# dc26_maneki-neko_badge_page01_2018060723.net
KiCad netlist of a schematic drawn in EAGLE
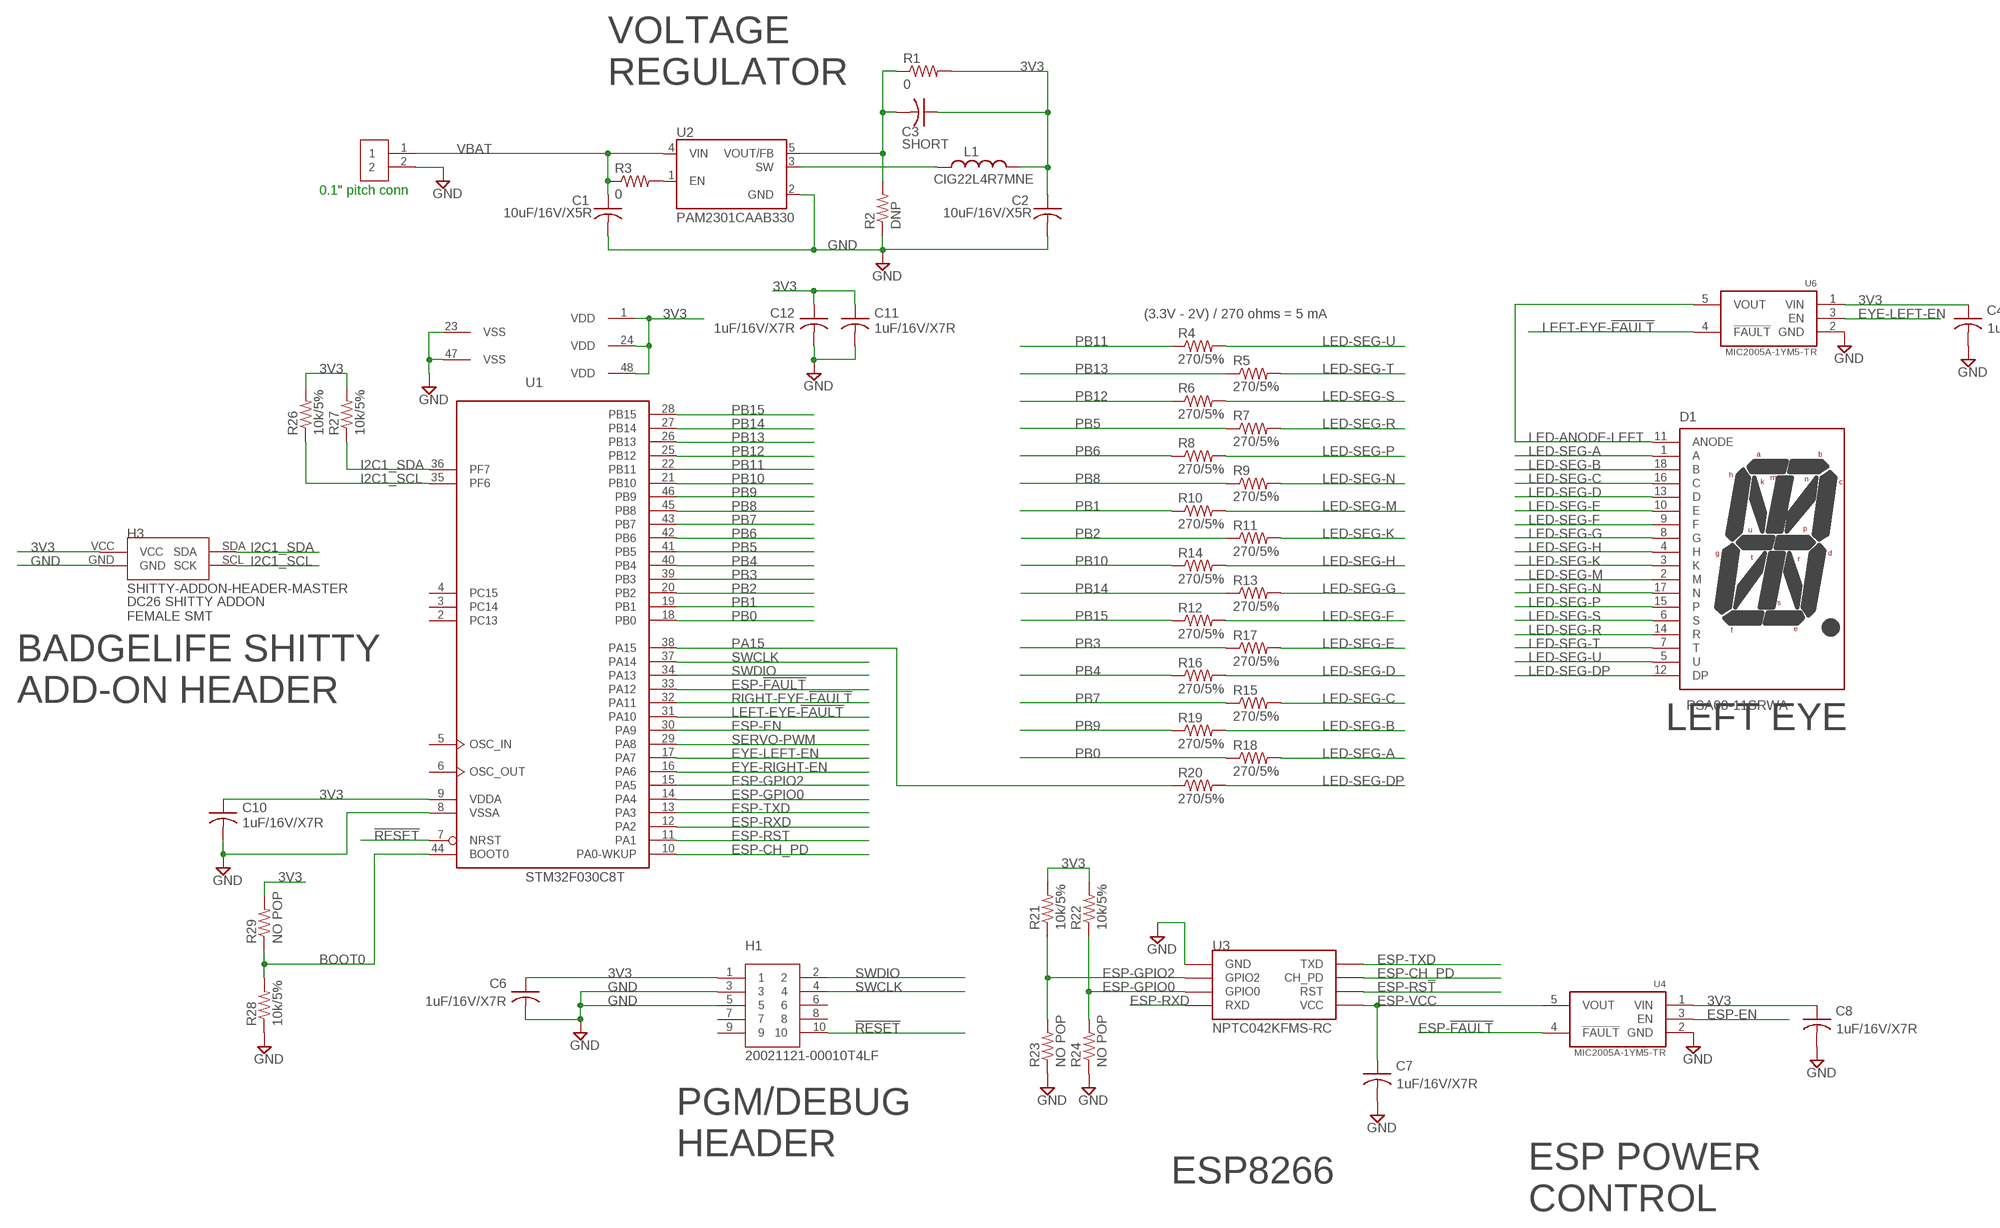
[diagram p0: schematic, sheet 1, part 1 of 2]
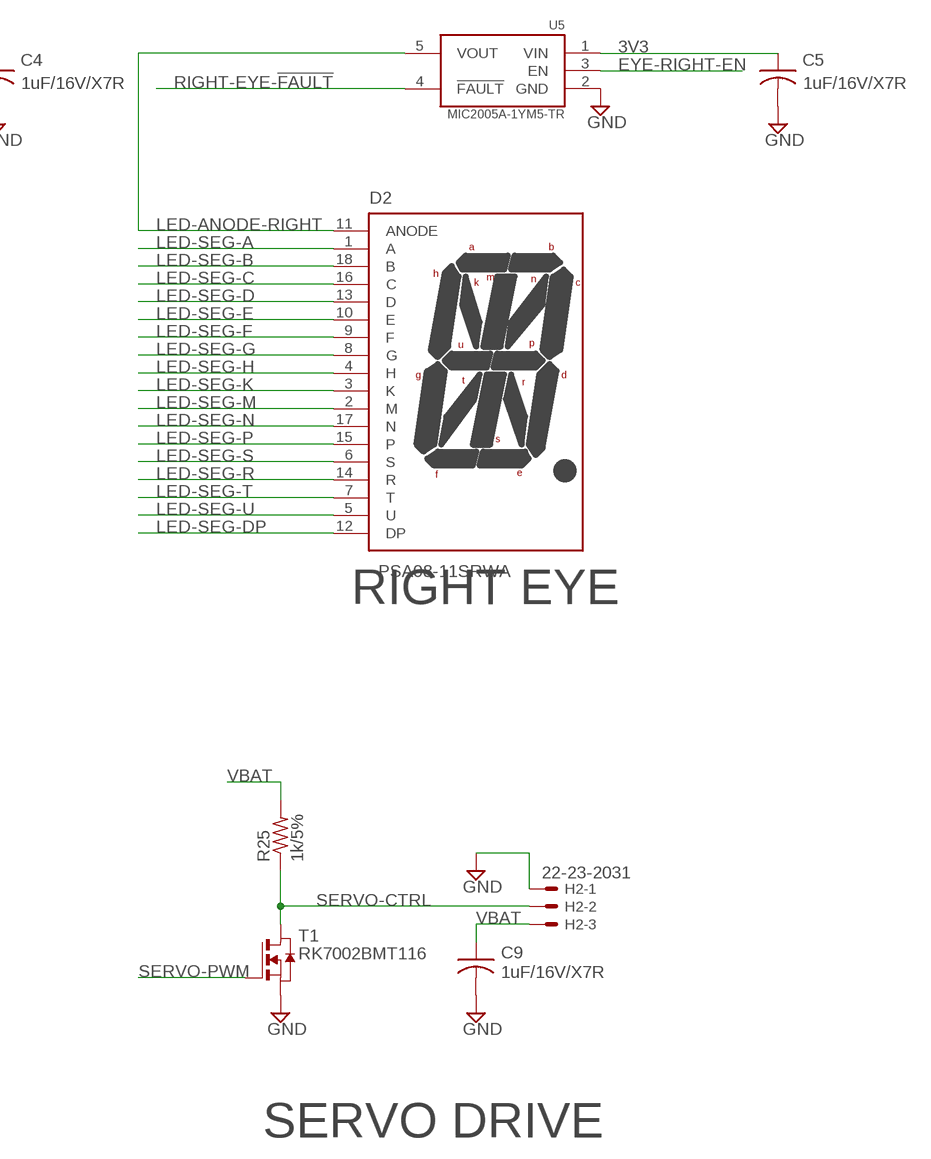
[diagram p1: schematic, sheet 1, part 2 of 2]

(export (version "E")
  (design (tool "Eeschema 10.0.6"))
  (components
    (comp (ref "C1")
      (value "10uF/16V/X5R")
      (footprint "eagle-import:C0805")
      (libsource (lib "eagle-import") (part "C-USC0805"))
    )
    (comp (ref "C2")
      (value "10uF/16V/X5R")
      (footprint "eagle-import:C0805")
      (libsource (lib "eagle-import") (part "C-USC0805"))
    )
    (comp (ref "C3")
      (value "SHORT")
      (footprint "eagle-import:C0805")
      (libsource (lib "eagle-import") (part "C-USC0805"))
    )
    (comp (ref "C4")
      (value "1uF/16V/X7R")
      (footprint "eagle-import:C0805")
      (libsource (lib "eagle-import") (part "C-USC0805"))
    )
    (comp (ref "C5")
      (value "1uF/16V/X7R")
      (footprint "eagle-import:C0805")
      (libsource (lib "eagle-import") (part "C-USC0805"))
    )
    (comp (ref "C6")
      (value "1uF/16V/X7R")
      (footprint "eagle-import:C0805")
      (libsource (lib "eagle-import") (part "C-USC0805"))
    )
    (comp (ref "C7")
      (value "1uF/16V/X7R")
      (footprint "eagle-import:C0805")
      (libsource (lib "eagle-import") (part "C-USC0805"))
    )
    (comp (ref "C8")
      (value "1uF/16V/X7R")
      (footprint "eagle-import:C0805")
      (libsource (lib "eagle-import") (part "C-USC0805"))
    )
    (comp (ref "C9")
      (value "1uF/16V/X7R")
      (footprint "eagle-import:C0805")
      (libsource (lib "eagle-import") (part "C-USC0805"))
    )
    (comp (ref "C10")
      (value "1uF/16V/X7R")
      (footprint "eagle-import:C0805")
      (libsource (lib "eagle-import") (part "C-USC0805"))
    )
    (comp (ref "C11")
      (value "1uF/16V/X7R")
      (footprint "eagle-import:C0805")
      (libsource (lib "eagle-import") (part "C-USC0805"))
    )
    (comp (ref "C12")
      (value "1uF/16V/X7R")
      (footprint "eagle-import:C0805")
      (libsource (lib "eagle-import") (part "C-USC0805"))
    )
    (comp (ref "D1")
      (value "PSA08-11SRWA")
      (footprint "eagle-import:PSA08-11SRWA")
      (libsource (lib "eagle-import") (part "PSA08-11SRWA"))
    )
    (comp (ref "D2")
      (value "PSA08-11SRWA")
      (footprint "eagle-import:PSA08-11SRWA")
      (libsource (lib "eagle-import") (part "PSA08-11SRWA"))
    )
    (comp (ref "H1")
      (value "20021121-00010T4LF")
      (footprint "eagle-import:20021121-00010T4LF")
      (libsource (lib "eagle-import") (part "20021121-00010T4LF"))
    )
    (comp (ref "H2")
      (value "22-23-2031")
      (footprint "eagle-import:22-23-2031")
      (fields (field (name "MF") "MOLEX"))
      (libsource (lib "eagle-import") (part "22-23-2031"))
    )
    (comp (ref "H3")
      (value "SHITTY-ADDON-HEADER-MASTER")
      (footprint "eagle-import:2X2-0.1INCH-FEMALE-SMT")
      (libsource (lib "eagle-import") (part "SHITTY-ADDON-HEADER-MASTER"))
    )
    (comp (ref "L1")
      (value "CIG22L4R7MNE")
      (footprint "eagle-import:L-1008-US")
      (libsource (lib "eagle-import") (part "CIG22L4R7MNE"))
    )
    (comp (ref "R1")
      (value "0")
      (footprint "eagle-import:R0805")
      (libsource (lib "eagle-import") (part "R-US_R0805"))
    )
    (comp (ref "R2")
      (value "DNP")
      (footprint "eagle-import:R0805")
      (libsource (lib "eagle-import") (part "R-US_R0805"))
    )
    (comp (ref "R3")
      (value "0")
      (footprint "eagle-import:R0805")
      (libsource (lib "eagle-import") (part "R-US_R0805"))
    )
    (comp (ref "R4")
      (value "270/5%")
      (footprint "eagle-import:R0805")
      (libsource (lib "eagle-import") (part "R-US_R0805"))
    )
    (comp (ref "R5")
      (value "270/5%")
      (footprint "eagle-import:R0805")
      (libsource (lib "eagle-import") (part "R-US_R0805"))
    )
    (comp (ref "R6")
      (value "270/5%")
      (footprint "eagle-import:R0805")
      (libsource (lib "eagle-import") (part "R-US_R0805"))
    )
    (comp (ref "R7")
      (value "270/5%")
      (footprint "eagle-import:R0805")
      (libsource (lib "eagle-import") (part "R-US_R0805"))
    )
    (comp (ref "R8")
      (value "270/5%")
      (footprint "eagle-import:R0805")
      (libsource (lib "eagle-import") (part "R-US_R0805"))
    )
    (comp (ref "R9")
      (value "270/5%")
      (footprint "eagle-import:R0805")
      (libsource (lib "eagle-import") (part "R-US_R0805"))
    )
    (comp (ref "R10")
      (value "270/5%")
      (footprint "eagle-import:R0805")
      (libsource (lib "eagle-import") (part "R-US_R0805"))
    )
    (comp (ref "R11")
      (value "270/5%")
      (footprint "eagle-import:R0805")
      (libsource (lib "eagle-import") (part "R-US_R0805"))
    )
    (comp (ref "R12")
      (value "270/5%")
      (footprint "eagle-import:R0805")
      (libsource (lib "eagle-import") (part "R-US_R0805"))
    )
    (comp (ref "R13")
      (value "270/5%")
      (footprint "eagle-import:R0805")
      (libsource (lib "eagle-import") (part "R-US_R0805"))
    )
    (comp (ref "R14")
      (value "270/5%")
      (footprint "eagle-import:R0805")
      (libsource (lib "eagle-import") (part "R-US_R0805"))
    )
    (comp (ref "R15")
      (value "270/5%")
      (footprint "eagle-import:R0805")
      (libsource (lib "eagle-import") (part "R-US_R0805"))
    )
    (comp (ref "R16")
      (value "270/5%")
      (footprint "eagle-import:R0805")
      (libsource (lib "eagle-import") (part "R-US_R0805"))
    )
    (comp (ref "R17")
      (value "270/5%")
      (footprint "eagle-import:R0805")
      (libsource (lib "eagle-import") (part "R-US_R0805"))
    )
    (comp (ref "R18")
      (value "270/5%")
      (footprint "eagle-import:R0805")
      (libsource (lib "eagle-import") (part "R-US_R0805"))
    )
    (comp (ref "R19")
      (value "270/5%")
      (footprint "eagle-import:R0805")
      (libsource (lib "eagle-import") (part "R-US_R0805"))
    )
    (comp (ref "R20")
      (value "270/5%")
      (footprint "eagle-import:R0805")
      (libsource (lib "eagle-import") (part "R-US_R0805"))
    )
    (comp (ref "R21")
      (value "10k/5%")
      (footprint "eagle-import:R0805")
      (libsource (lib "eagle-import") (part "R-US_R0805"))
    )
    (comp (ref "R22")
      (value "10k/5%")
      (footprint "eagle-import:R0805")
      (libsource (lib "eagle-import") (part "R-US_R0805"))
    )
    (comp (ref "R23")
      (value "NO POP")
      (footprint "eagle-import:R0805")
      (libsource (lib "eagle-import") (part "R-US_R0805"))
    )
    (comp (ref "R24")
      (value "NO POP")
      (footprint "eagle-import:R0805")
      (libsource (lib "eagle-import") (part "R-US_R0805"))
    )
    (comp (ref "R25")
      (value "1k/5%")
      (footprint "eagle-import:R0805")
      (libsource (lib "eagle-import") (part "R-US_R0805"))
    )
    (comp (ref "R26")
      (value "10k/5%")
      (footprint "eagle-import:R0805")
      (libsource (lib "eagle-import") (part "R-US_R0805"))
    )
    (comp (ref "R27")
      (value "10k/5%")
      (footprint "eagle-import:R0805")
      (libsource (lib "eagle-import") (part "R-US_R0805"))
    )
    (comp (ref "R28")
      (value "10k/5%")
      (footprint "eagle-import:R0805")
      (libsource (lib "eagle-import") (part "R-US_R0805"))
    )
    (comp (ref "R29")
      (value "NO POP")
      (footprint "eagle-import:R0805")
      (libsource (lib "eagle-import") (part "R-US_R0805"))
    )
    (comp (ref "T1")
      (value "RK7002BMT116")
      (footprint "eagle-import:SOT-23")
      (libsource (lib "eagle-import") (part "NMOSSOT23"))
    )
    (comp (ref "U$1")
      (value "BATTPADS-SMT")
      (footprint "eagle-import:BATTPADS-SMT")
      (libsource (lib "eagle-import") (part "BATTPADS-SMT"))
    )
    (comp (ref "U1")
      (value "STM32F030C8T")
      (footprint "eagle-import:LQFP48")
      (libsource (lib "eagle-import") (part "STM32F030CT8"))
    )
    (comp (ref "U2")
      (value "PAM2301CAAB330")
      (footprint "eagle-import:SOT95P280X100-5N")
      (libsource (lib "eagle-import") (part "PAM2301CAAB330"))
    )
    (comp (ref "U3")
      (value "NPTC042KFMS-RC")
      (footprint "eagle-import:NPTC042KFMS-RC")
      (libsource (lib "eagle-import") (part "NPTC042KFMS-RC"))
    )
    (comp (ref "U4")
      (value "MIC2005A-1YM5-TR")
      (footprint "eagle-import:SOT95P270X145-5N")
      (libsource (lib "eagle-import") (part "MIC2005A-1YM5-TR"))
    )
    (comp (ref "U5")
      (value "MIC2005A-1YM5-TR")
      (footprint "eagle-import:SOT95P270X145-5N")
      (libsource (lib "eagle-import") (part "MIC2005A-1YM5-TR"))
    )
    (comp (ref "U6")
      (value "MIC2005A-1YM5-TR")
      (footprint "eagle-import:SOT95P270X145-5N")
      (libsource (lib "eagle-import") (part "MIC2005A-1YM5-TR"))
    )
  )
  (nets
    (net (code "1") (name "/3V3") (class "Default")
      (node (ref "C10") (pin "1") (pinfunction "1_1") (pintype "passive"))
      (node (ref "C11") (pin "1") (pinfunction "1_1") (pintype "passive"))
      (node (ref "C12") (pin "1") (pinfunction "1_1") (pintype "passive"))
      (node (ref "C2") (pin "1") (pinfunction "1_1") (pintype "passive"))
      (node (ref "C3") (pin "1") (pinfunction "1_1") (pintype "passive"))
      (node (ref "C4") (pin "1") (pinfunction "1_1") (pintype "passive"))
      (node (ref "C5") (pin "1") (pinfunction "1_1") (pintype "passive"))
      (node (ref "C6") (pin "1") (pinfunction "1_1") (pintype "passive"))
      (node (ref "C8") (pin "1") (pinfunction "1_1") (pintype "passive"))
      (node (ref "H1") (pin "1") (pinfunction "1_1") (pintype "bidirectional"))
      (node (ref "H3") (pin "VCC") (pinfunction "VCC_VCC") (pintype "bidirectional"))
      (node (ref "L1") (pin "P$2") (pinfunction "2_P$2") (pintype "passive"))
      (node (ref "R1") (pin "2") (pinfunction "2_2") (pintype "passive"))
      (node (ref "R21") (pin "2") (pinfunction "2_2") (pintype "passive"))
      (node (ref "R22") (pin "2") (pinfunction "2_2") (pintype "passive"))
      (node (ref "R26") (pin "2") (pinfunction "2_2") (pintype "passive"))
      (node (ref "R27") (pin "2") (pinfunction "2_2") (pintype "passive"))
      (node (ref "R29") (pin "2") (pinfunction "2_2") (pintype "passive"))
      (node (ref "U1") (pin "1") (pinfunction "VDD_1") (pintype "power_in"))
      (node (ref "U1") (pin "24") (pinfunction "VDD_24") (pintype "power_in"))
      (node (ref "U1") (pin "48") (pinfunction "VDD_48") (pintype "power_in"))
      (node (ref "U1") (pin "9") (pinfunction "VDDA_9") (pintype "power_in"))
      (node (ref "U4") (pin "1") (pinfunction "VIN_1") (pintype "bidirectional"))
      (node (ref "U5") (pin "1") (pinfunction "VIN_1") (pintype "bidirectional"))
      (node (ref "U6") (pin "1") (pinfunction "VIN_1") (pintype "bidirectional"))
    )
    (net (code "2") (name "/BOOT0") (class "Default")
      (node (ref "R28") (pin "2") (pinfunction "2_2") (pintype "passive"))
      (node (ref "R29") (pin "1") (pinfunction "1_1") (pintype "passive"))
      (node (ref "U1") (pin "44") (pinfunction "BOOT0_44") (pintype "input"))
    )
    (net (code "3") (name "/ESP-CH_PD") (class "Default")
      (node (ref "U1") (pin "10") (pinfunction "PA0-WKUP_10") (pintype "bidirectional"))
      (node (ref "U3") (pin "3") (pinfunction "CH_PD_3") (pintype "bidirectional"))
    )
    (net (code "4") (name "/ESP-EN") (class "Default")
      (node (ref "U1") (pin "30") (pinfunction "PA9_30") (pintype "bidirectional"))
      (node (ref "U4") (pin "3") (pinfunction "EN_3") (pintype "bidirectional"))
    )
    (net (code "5") (name "/ESP-GPIO0") (class "Default")
      (node (ref "R22") (pin "1") (pinfunction "1_1") (pintype "passive"))
      (node (ref "R24") (pin "2") (pinfunction "2_2") (pintype "passive"))
      (node (ref "U1") (pin "14") (pinfunction "PA4_14") (pintype "bidirectional"))
      (node (ref "U3") (pin "6") (pinfunction "GPIO0_6") (pintype "bidirectional"))
    )
    (net (code "6") (name "/ESP-GPIO2") (class "Default")
      (node (ref "R21") (pin "1") (pinfunction "1_1") (pintype "passive"))
      (node (ref "R23") (pin "2") (pinfunction "2_2") (pintype "passive"))
      (node (ref "U1") (pin "15") (pinfunction "PA5_15") (pintype "bidirectional"))
      (node (ref "U3") (pin "4") (pinfunction "GPIO2_4") (pintype "bidirectional"))
    )
    (net (code "7") (name "/ESP-RST") (class "Default")
      (node (ref "U1") (pin "11") (pinfunction "PA1_11") (pintype "bidirectional"))
      (node (ref "U3") (pin "5") (pinfunction "RST_5") (pintype "bidirectional"))
    )
    (net (code "8") (name "/ESP-RXD") (class "Default")
      (node (ref "U1") (pin "12") (pinfunction "PA2_12") (pintype "bidirectional"))
      (node (ref "U3") (pin "8") (pinfunction "RXD_8") (pintype "bidirectional"))
    )
    (net (code "9") (name "/ESP-TXD") (class "Default")
      (node (ref "U1") (pin "13") (pinfunction "PA3_13") (pintype "bidirectional"))
      (node (ref "U3") (pin "1") (pinfunction "TXD_1") (pintype "bidirectional"))
    )
    (net (code "10") (name "/ESP-VCC") (class "Default")
      (node (ref "C7") (pin "1") (pinfunction "1_1") (pintype "passive"))
      (node (ref "U3") (pin "7") (pinfunction "VCC_7") (pintype "bidirectional"))
      (node (ref "U4") (pin "5") (pinfunction "VOUT_5") (pintype "bidirectional"))
    )
    (net (code "11") (name "/ESP-~{FAULT}") (class "Default")
      (node (ref "U1") (pin "33") (pinfunction "PA12_33") (pintype "bidirectional"))
      (node (ref "U4") (pin "4") (pinfunction "~{FAULT}_4") (pintype "bidirectional"))
    )
    (net (code "12") (name "/EYE-LEFT-EN") (class "Default")
      (node (ref "U1") (pin "17") (pinfunction "PA7_17") (pintype "bidirectional"))
      (node (ref "U6") (pin "3") (pinfunction "EN_3") (pintype "bidirectional"))
    )
    (net (code "13") (name "/EYE-RIGHT-EN") (class "Default")
      (node (ref "U1") (pin "16") (pinfunction "PA6_16") (pintype "bidirectional"))
      (node (ref "U5") (pin "3") (pinfunction "EN_3") (pintype "bidirectional"))
    )
    (net (code "14") (name "/I2C1_SCL") (class "Default")
      (node (ref "H3") (pin "SCL") (pinfunction "SCK_SCL") (pintype "bidirectional"))
      (node (ref "R26") (pin "1") (pinfunction "1_1") (pintype "passive"))
      (node (ref "U1") (pin "35") (pinfunction "PF6_35") (pintype "bidirectional"))
    )
    (net (code "15") (name "/I2C1_SDA") (class "Default")
      (node (ref "H3") (pin "SDA") (pinfunction "SDA_SDA") (pintype "bidirectional"))
      (node (ref "R27") (pin "1") (pinfunction "1_1") (pintype "passive"))
      (node (ref "U1") (pin "36") (pinfunction "PF7_36") (pintype "bidirectional"))
    )
    (net (code "16") (name "/LED-ANODE-LEFT") (class "Default")
      (node (ref "D1") (pin "11") (pinfunction "ANODE_11") (pintype "bidirectional"))
      (node (ref "U6") (pin "5") (pinfunction "VOUT_5") (pintype "bidirectional"))
    )
    (net (code "17") (name "/LED-ANODE-RIGHT") (class "Default")
      (node (ref "D2") (pin "11") (pinfunction "ANODE_11") (pintype "bidirectional"))
      (node (ref "U5") (pin "5") (pinfunction "VOUT_5") (pintype "bidirectional"))
    )
    (net (code "18") (name "/LED-SEG-A") (class "Default")
      (node (ref "D1") (pin "1") (pinfunction "A_1") (pintype "bidirectional"))
      (node (ref "D2") (pin "1") (pinfunction "A_1") (pintype "bidirectional"))
      (node (ref "R18") (pin "2") (pinfunction "2_2") (pintype "passive"))
    )
    (net (code "19") (name "/LED-SEG-B") (class "Default")
      (node (ref "D1") (pin "18") (pinfunction "B_18") (pintype "bidirectional"))
      (node (ref "D2") (pin "18") (pinfunction "B_18") (pintype "bidirectional"))
      (node (ref "R19") (pin "2") (pinfunction "2_2") (pintype "passive"))
    )
    (net (code "20") (name "/LED-SEG-C") (class "Default")
      (node (ref "D1") (pin "16") (pinfunction "C_16") (pintype "bidirectional"))
      (node (ref "D2") (pin "16") (pinfunction "C_16") (pintype "bidirectional"))
      (node (ref "R15") (pin "2") (pinfunction "2_2") (pintype "passive"))
    )
    (net (code "21") (name "/LED-SEG-D") (class "Default")
      (node (ref "D1") (pin "13") (pinfunction "D_13") (pintype "bidirectional"))
      (node (ref "D2") (pin "13") (pinfunction "D_13") (pintype "bidirectional"))
      (node (ref "R16") (pin "2") (pinfunction "2_2") (pintype "passive"))
    )
    (net (code "22") (name "/LED-SEG-DP") (class "Default")
      (node (ref "D1") (pin "12") (pinfunction "DP_12") (pintype "bidirectional"))
      (node (ref "D2") (pin "12") (pinfunction "DP_12") (pintype "bidirectional"))
      (node (ref "R20") (pin "2") (pinfunction "2_2") (pintype "passive"))
    )
    (net (code "23") (name "/LED-SEG-E") (class "Default")
      (node (ref "D1") (pin "10") (pinfunction "E_10") (pintype "bidirectional"))
      (node (ref "D2") (pin "10") (pinfunction "E_10") (pintype "bidirectional"))
      (node (ref "R17") (pin "2") (pinfunction "2_2") (pintype "passive"))
    )
    (net (code "24") (name "/LED-SEG-F") (class "Default")
      (node (ref "D1") (pin "9") (pinfunction "F_9") (pintype "bidirectional"))
      (node (ref "D2") (pin "9") (pinfunction "F_9") (pintype "bidirectional"))
      (node (ref "R12") (pin "2") (pinfunction "2_2") (pintype "passive"))
    )
    (net (code "25") (name "/LED-SEG-G") (class "Default")
      (node (ref "D1") (pin "8") (pinfunction "G_8") (pintype "bidirectional"))
      (node (ref "D2") (pin "8") (pinfunction "G_8") (pintype "bidirectional"))
      (node (ref "R13") (pin "2") (pinfunction "2_2") (pintype "passive"))
    )
    (net (code "26") (name "/LED-SEG-H") (class "Default")
      (node (ref "D1") (pin "4") (pinfunction "H_4") (pintype "bidirectional"))
      (node (ref "D2") (pin "4") (pinfunction "H_4") (pintype "bidirectional"))
      (node (ref "R14") (pin "2") (pinfunction "2_2") (pintype "passive"))
    )
    (net (code "27") (name "/LED-SEG-K") (class "Default")
      (node (ref "D1") (pin "3") (pinfunction "K_3") (pintype "bidirectional"))
      (node (ref "D2") (pin "3") (pinfunction "K_3") (pintype "bidirectional"))
      (node (ref "R11") (pin "2") (pinfunction "2_2") (pintype "passive"))
    )
    (net (code "28") (name "/LED-SEG-M") (class "Default")
      (node (ref "D1") (pin "2") (pinfunction "M_2") (pintype "bidirectional"))
      (node (ref "D2") (pin "2") (pinfunction "M_2") (pintype "bidirectional"))
      (node (ref "R10") (pin "2") (pinfunction "2_2") (pintype "passive"))
    )
    (net (code "29") (name "/LED-SEG-N") (class "Default")
      (node (ref "D1") (pin "17") (pinfunction "N_17") (pintype "bidirectional"))
      (node (ref "D2") (pin "17") (pinfunction "N_17") (pintype "bidirectional"))
      (node (ref "R9") (pin "2") (pinfunction "2_2") (pintype "passive"))
    )
    (net (code "30") (name "/LED-SEG-P") (class "Default")
      (node (ref "D1") (pin "15") (pinfunction "P_15") (pintype "bidirectional"))
      (node (ref "D2") (pin "15") (pinfunction "P_15") (pintype "bidirectional"))
      (node (ref "R8") (pin "2") (pinfunction "2_2") (pintype "passive"))
    )
    (net (code "31") (name "/LED-SEG-R") (class "Default")
      (node (ref "D1") (pin "14") (pinfunction "R_14") (pintype "bidirectional"))
      (node (ref "D2") (pin "14") (pinfunction "R_14") (pintype "bidirectional"))
      (node (ref "R7") (pin "2") (pinfunction "2_2") (pintype "passive"))
    )
    (net (code "32") (name "/LED-SEG-S") (class "Default")
      (node (ref "D1") (pin "6") (pinfunction "S_6") (pintype "bidirectional"))
      (node (ref "D2") (pin "6") (pinfunction "S_6") (pintype "bidirectional"))
      (node (ref "R6") (pin "2") (pinfunction "2_2") (pintype "passive"))
    )
    (net (code "33") (name "/LED-SEG-T") (class "Default")
      (node (ref "D1") (pin "7") (pinfunction "T_7") (pintype "bidirectional"))
      (node (ref "D2") (pin "7") (pinfunction "T_7") (pintype "bidirectional"))
      (node (ref "R5") (pin "2") (pinfunction "2_2") (pintype "passive"))
    )
    (net (code "34") (name "/LED-SEG-U") (class "Default")
      (node (ref "D1") (pin "5") (pinfunction "U_5") (pintype "bidirectional"))
      (node (ref "D2") (pin "5") (pinfunction "U_5") (pintype "bidirectional"))
      (node (ref "R4") (pin "2") (pinfunction "2_2") (pintype "passive"))
    )
    (net (code "35") (name "/LEFT-EYE-~{FAULT}") (class "Default")
      (node (ref "U1") (pin "31") (pinfunction "PA10_31") (pintype "bidirectional"))
      (node (ref "U6") (pin "4") (pinfunction "~{FAULT}_4") (pintype "bidirectional"))
    )
    (net (code "36") (name "/PA15") (class "Default")
      (node (ref "R20") (pin "1") (pinfunction "1_1") (pintype "passive"))
      (node (ref "U1") (pin "38") (pinfunction "PA15_38") (pintype "bidirectional"))
    )
    (net (code "37") (name "/PB0") (class "Default")
      (node (ref "R18") (pin "1") (pinfunction "1_1") (pintype "passive"))
      (node (ref "U1") (pin "18") (pinfunction "PB0_18") (pintype "bidirectional"))
    )
    (net (code "38") (name "/PB1") (class "Default")
      (node (ref "R10") (pin "1") (pinfunction "1_1") (pintype "passive"))
      (node (ref "U1") (pin "19") (pinfunction "PB1_19") (pintype "bidirectional"))
    )
    (net (code "39") (name "/PB2") (class "Default")
      (node (ref "R11") (pin "1") (pinfunction "1_1") (pintype "passive"))
      (node (ref "U1") (pin "20") (pinfunction "PB2_20") (pintype "bidirectional"))
    )
    (net (code "40") (name "/PB3") (class "Default")
      (node (ref "R17") (pin "1") (pinfunction "1_1") (pintype "passive"))
      (node (ref "U1") (pin "39") (pinfunction "PB3_39") (pintype "bidirectional"))
    )
    (net (code "41") (name "/PB4") (class "Default")
      (node (ref "R16") (pin "1") (pinfunction "1_1") (pintype "passive"))
      (node (ref "U1") (pin "40") (pinfunction "PB4_40") (pintype "bidirectional"))
    )
    (net (code "42") (name "/PB5") (class "Default")
      (node (ref "R7") (pin "1") (pinfunction "1_1") (pintype "passive"))
      (node (ref "U1") (pin "41") (pinfunction "PB5_41") (pintype "bidirectional"))
    )
    (net (code "43") (name "/PB6") (class "Default")
      (node (ref "R8") (pin "1") (pinfunction "1_1") (pintype "passive"))
      (node (ref "U1") (pin "42") (pinfunction "PB6_42") (pintype "bidirectional"))
    )
    (net (code "44") (name "/PB7") (class "Default")
      (node (ref "R15") (pin "1") (pinfunction "1_1") (pintype "passive"))
      (node (ref "U1") (pin "43") (pinfunction "PB7_43") (pintype "bidirectional"))
    )
    (net (code "45") (name "/PB8") (class "Default")
      (node (ref "R9") (pin "1") (pinfunction "1_1") (pintype "passive"))
      (node (ref "U1") (pin "45") (pinfunction "PB8_45") (pintype "bidirectional"))
    )
    (net (code "46") (name "/PB9") (class "Default")
      (node (ref "R19") (pin "1") (pinfunction "1_1") (pintype "passive"))
      (node (ref "U1") (pin "46") (pinfunction "PB9_46") (pintype "bidirectional"))
    )
    (net (code "47") (name "/PB10") (class "Default")
      (node (ref "R14") (pin "1") (pinfunction "1_1") (pintype "passive"))
      (node (ref "U1") (pin "21") (pinfunction "PB10_21") (pintype "bidirectional"))
    )
    (net (code "48") (name "/PB11") (class "Default")
      (node (ref "R4") (pin "1") (pinfunction "1_1") (pintype "passive"))
      (node (ref "U1") (pin "22") (pinfunction "PB11_22") (pintype "bidirectional"))
    )
    (net (code "49") (name "/PB12") (class "Default")
      (node (ref "R6") (pin "1") (pinfunction "1_1") (pintype "passive"))
      (node (ref "U1") (pin "25") (pinfunction "PB12_25") (pintype "bidirectional"))
    )
    (net (code "50") (name "/PB13") (class "Default")
      (node (ref "R5") (pin "1") (pinfunction "1_1") (pintype "passive"))
      (node (ref "U1") (pin "26") (pinfunction "PB13_26") (pintype "bidirectional"))
    )
    (net (code "51") (name "/PB14") (class "Default")
      (node (ref "R13") (pin "1") (pinfunction "1_1") (pintype "passive"))
      (node (ref "U1") (pin "27") (pinfunction "PB14_27") (pintype "bidirectional"))
    )
    (net (code "52") (name "/PB15") (class "Default")
      (node (ref "R12") (pin "1") (pinfunction "1_1") (pintype "passive"))
      (node (ref "U1") (pin "28") (pinfunction "PB15_28") (pintype "bidirectional"))
    )
    (net (code "53") (name "/RIGHT-EYE-~{FAULT}") (class "Default")
      (node (ref "U1") (pin "32") (pinfunction "PA11_32") (pintype "bidirectional"))
      (node (ref "U5") (pin "4") (pinfunction "~{FAULT}_4") (pintype "bidirectional"))
    )
    (net (code "54") (name "/SERVO-CTRL") (class "Default")
      (node (ref "H2") (pin "2") (pinfunction "S_2") (pintype "passive"))
      (node (ref "R25") (pin "1") (pinfunction "1_1") (pintype "passive"))
      (node (ref "T1") (pin "1") (pinfunction "D_1") (pintype "passive"))
    )
    (net (code "55") (name "/SERVO-PWM") (class "Default")
      (node (ref "T1") (pin "3") (pinfunction "G_3") (pintype "passive"))
      (node (ref "U1") (pin "29") (pinfunction "PA8_29") (pintype "bidirectional"))
    )
    (net (code "56") (name "/SWCLK") (class "Default")
      (node (ref "H1") (pin "4") (pinfunction "4_4") (pintype "bidirectional"))
      (node (ref "U1") (pin "37") (pinfunction "PA14_37") (pintype "bidirectional"))
    )
    (net (code "57") (name "/SWDIO") (class "Default")
      (node (ref "H1") (pin "2") (pinfunction "2_2") (pintype "bidirectional"))
      (node (ref "U1") (pin "34") (pinfunction "PA13_34") (pintype "bidirectional"))
    )
    (net (code "58") (name "/VBAT") (class "Default")
      (node (ref "C1") (pin "1") (pinfunction "1_1") (pintype "passive"))
      (node (ref "C9") (pin "1") (pinfunction "1_1") (pintype "passive"))
      (node (ref "H2") (pin "3") (pinfunction "S_3") (pintype "passive"))
      (node (ref "R25") (pin "2") (pinfunction "2_2") (pintype "passive"))
      (node (ref "R3") (pin "1") (pinfunction "1_1") (pintype "passive"))
      (node (ref "U$1") (pin "1") (pinfunction "1_1") (pintype "bidirectional"))
      (node (ref "U2") (pin "4") (pinfunction "VIN_4") (pintype "input"))
    )
    (net (code "59") (name "/~{RESET}") (class "Default")
      (node (ref "H1") (pin "10") (pinfunction "10_10") (pintype "bidirectional"))
      (node (ref "U1") (pin "7") (pinfunction "NRST_7") (pintype "bidirectional"))
    )
    (net (code "60") (name "GND") (class "Default")
      (node (ref "C1") (pin "2") (pinfunction "2_2") (pintype "passive"))
      (node (ref "C10") (pin "2") (pinfunction "2_2") (pintype "passive"))
      (node (ref "C11") (pin "2") (pinfunction "2_2") (pintype "passive"))
      (node (ref "C12") (pin "2") (pinfunction "2_2") (pintype "passive"))
      (node (ref "C2") (pin "2") (pinfunction "2_2") (pintype "passive"))
      (node (ref "C4") (pin "2") (pinfunction "2_2") (pintype "passive"))
      (node (ref "C5") (pin "2") (pinfunction "2_2") (pintype "passive"))
      (node (ref "C6") (pin "2") (pinfunction "2_2") (pintype "passive"))
      (node (ref "C7") (pin "2") (pinfunction "2_2") (pintype "passive"))
      (node (ref "C8") (pin "2") (pinfunction "2_2") (pintype "passive"))
      (node (ref "C9") (pin "2") (pinfunction "2_2") (pintype "passive"))
      (node (ref "H1") (pin "3") (pinfunction "3_3") (pintype "bidirectional"))
      (node (ref "H1") (pin "5") (pinfunction "5_5") (pintype "bidirectional"))
      (node (ref "H2") (pin "1") (pinfunction "S_1") (pintype "passive"))
      (node (ref "H3") (pin "GND") (pinfunction "GND_GND") (pintype "bidirectional"))
      (node (ref "R2") (pin "1") (pinfunction "1_1") (pintype "passive"))
      (node (ref "R23") (pin "1") (pinfunction "1_1") (pintype "passive"))
      (node (ref "R24") (pin "1") (pinfunction "1_1") (pintype "passive"))
      (node (ref "R28") (pin "1") (pinfunction "1_1") (pintype "passive"))
      (node (ref "T1") (pin "2") (pinfunction "S_2") (pintype "passive"))
      (node (ref "U$1") (pin "2") (pinfunction "2_2") (pintype "bidirectional"))
      (node (ref "U1") (pin "23") (pinfunction "VSS_23") (pintype "power_in"))
      (node (ref "U1") (pin "47") (pinfunction "VSS_47") (pintype "power_in"))
      (node (ref "U1") (pin "8") (pinfunction "VSSA_8") (pintype "power_in"))
      (node (ref "U2") (pin "2") (pinfunction "GND_2") (pintype "power_in"))
      (node (ref "U3") (pin "2") (pinfunction "GND_2") (pintype "bidirectional"))
      (node (ref "U4") (pin "2") (pinfunction "GND_2") (pintype "bidirectional"))
      (node (ref "U5") (pin "2") (pinfunction "GND_2") (pintype "bidirectional"))
      (node (ref "U6") (pin "2") (pinfunction "GND_2") (pintype "bidirectional"))
    )
    (net (code "61") (name "Net-(L1-1)") (class "Default")
      (node (ref "L1") (pin "P$1") (pinfunction "1_P$1") (pintype "passive"))
      (node (ref "U2") (pin "3") (pinfunction "SW_3") (pintype "output"))
    )
    (net (code "62") (name "Net-(U2-EN)") (class "Default")
      (node (ref "R3") (pin "2") (pinfunction "2_2") (pintype "passive"))
      (node (ref "U2") (pin "1") (pinfunction "EN_1") (pintype "input"))
    )
    (net (code "63") (name "Net-(U2-VOUT{slash}FB)") (class "Default")
      (node (ref "C3") (pin "2") (pinfunction "2_2") (pintype "passive"))
      (node (ref "R1") (pin "1") (pinfunction "1_1") (pintype "passive"))
      (node (ref "R2") (pin "2") (pinfunction "2_2") (pintype "passive"))
      (node (ref "U2") (pin "5") (pinfunction "VOUT/FB_5") (pintype "output"))
    )
    (net (code "64") (name "unconnected-(H1-Pad6)") (class "Default")
      (node (ref "H1") (pin "6") (pinfunction "6_6") (pintype "bidirectional"))
    )
    (net (code "65") (name "unconnected-(H1-Pad7)") (class "Default")
      (node (ref "H1") (pin "7") (pinfunction "7_7") (pintype "bidirectional"))
    )
    (net (code "66") (name "unconnected-(H1-Pad8)") (class "Default")
      (node (ref "H1") (pin "8") (pinfunction "8_8") (pintype "bidirectional"))
    )
    (net (code "67") (name "unconnected-(H1-Pad9)") (class "Default")
      (node (ref "H1") (pin "9") (pinfunction "9_9") (pintype "bidirectional"))
    )
    (net (code "68") (name "unconnected-(U1A-OSC_IN-Pad5)") (class "Default")
      (node (ref "U1") (pin "5") (pinfunction "OSC_IN_5") (pintype "bidirectional"))
    )
    (net (code "69") (name "unconnected-(U1A-OSC_OUT-Pad6)") (class "Default")
      (node (ref "U1") (pin "6") (pinfunction "OSC_OUT_6") (pintype "bidirectional"))
    )
    (net (code "70") (name "unconnected-(U1A-PC13-Pad2)") (class "Default")
      (node (ref "U1") (pin "2") (pinfunction "PC13_2") (pintype "bidirectional"))
    )
    (net (code "71") (name "unconnected-(U1A-PC14-Pad3)") (class "Default")
      (node (ref "U1") (pin "3") (pinfunction "PC14_3") (pintype "bidirectional"))
    )
    (net (code "72") (name "unconnected-(U1A-PC15-Pad4)") (class "Default")
      (node (ref "U1") (pin "4") (pinfunction "PC15_4") (pintype "bidirectional"))
    )
  )
)
